# DigitalClockV2sch.net
KiCad netlist of a schematic drawn in Altium Designer
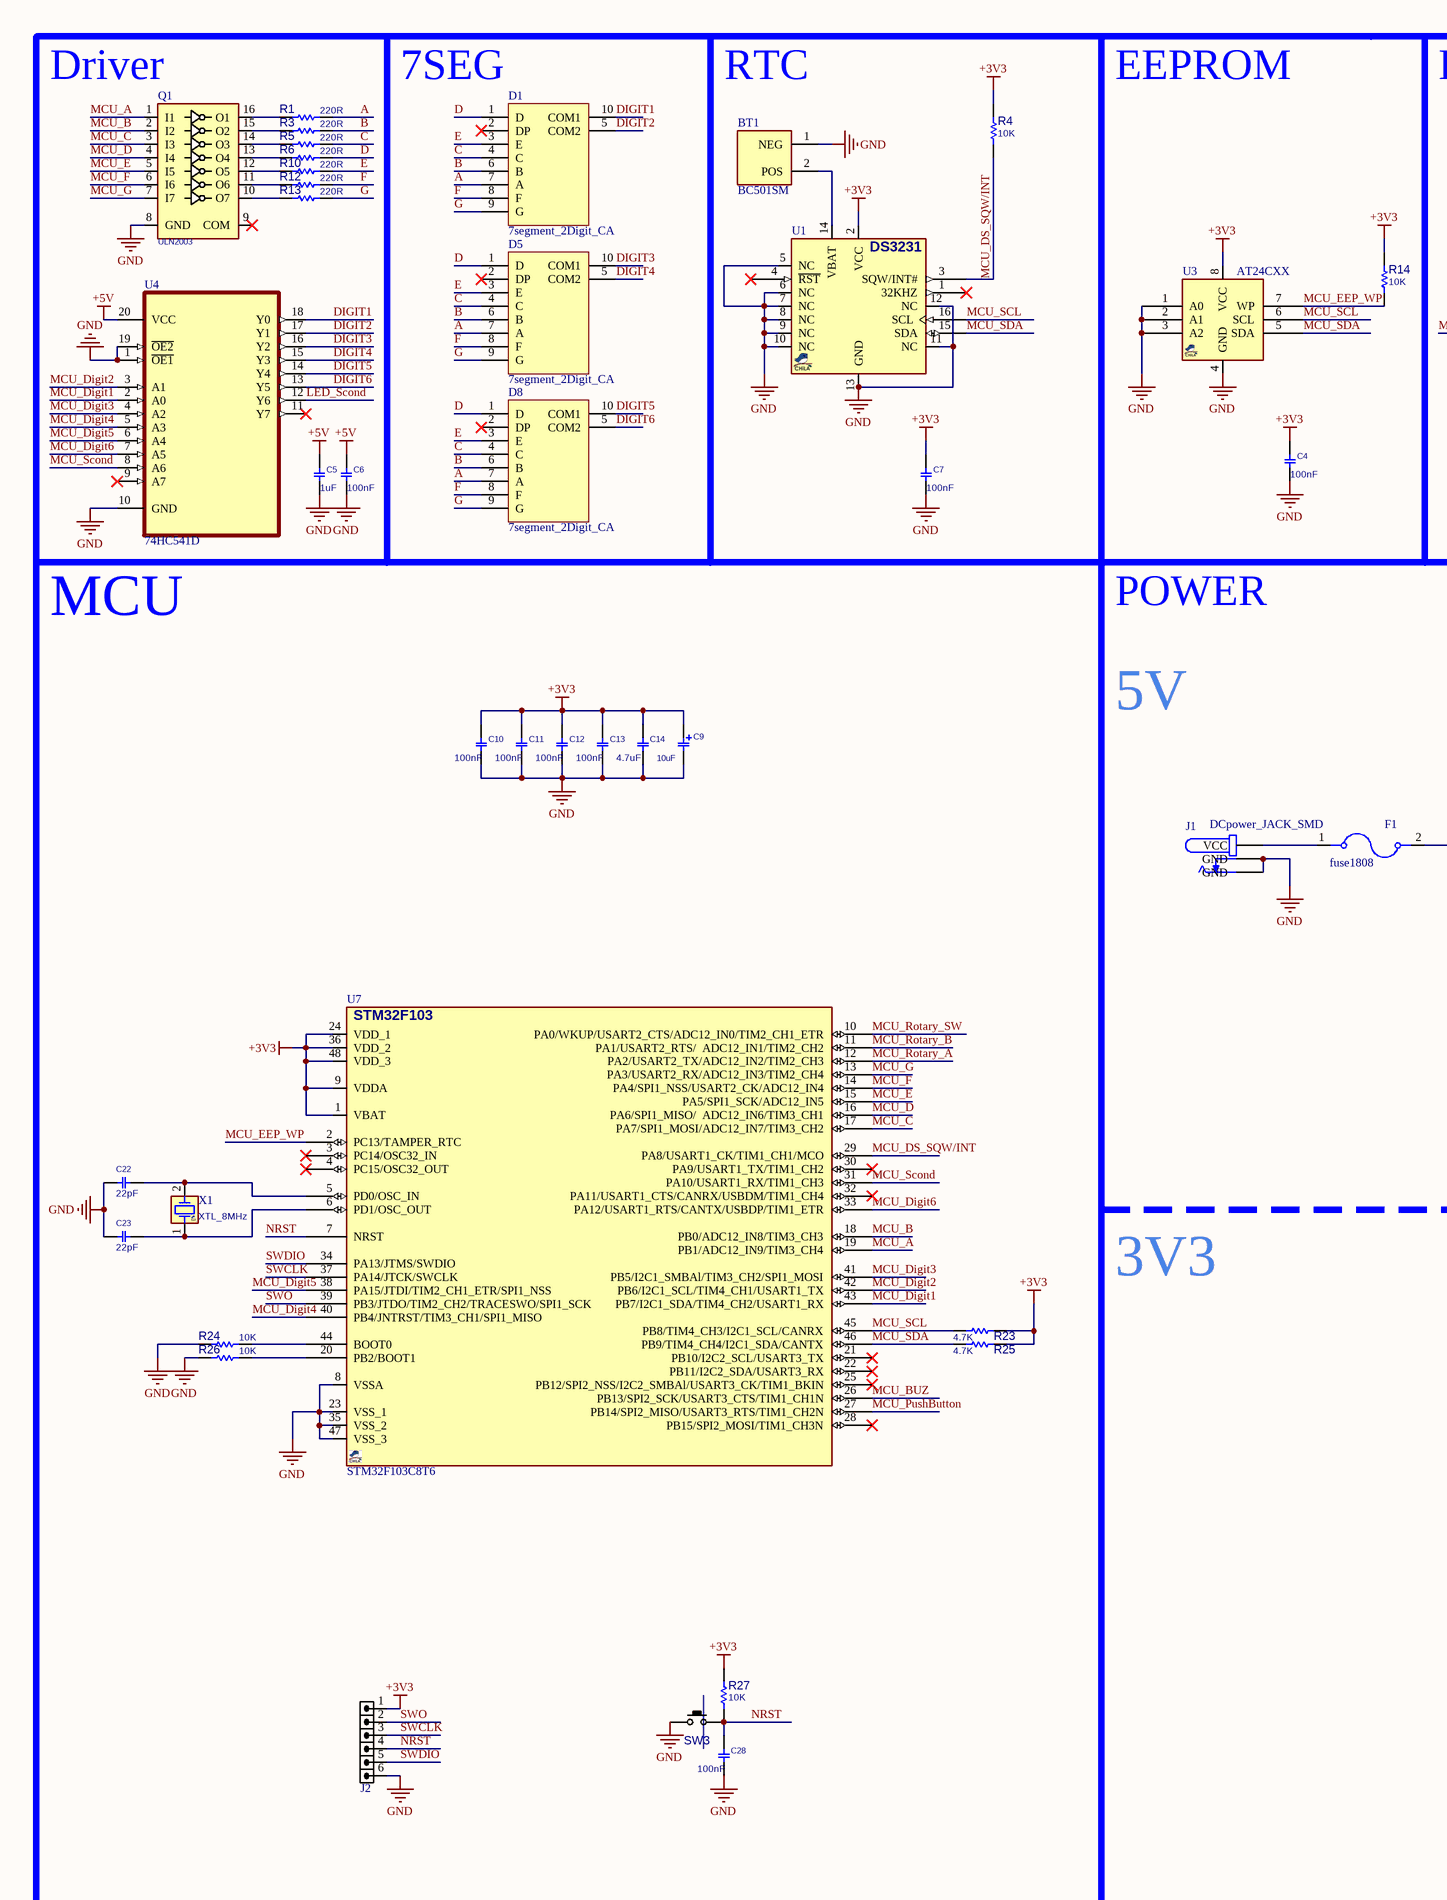
[diagram p0: DigitalClockV2sch.SchDoc, left]
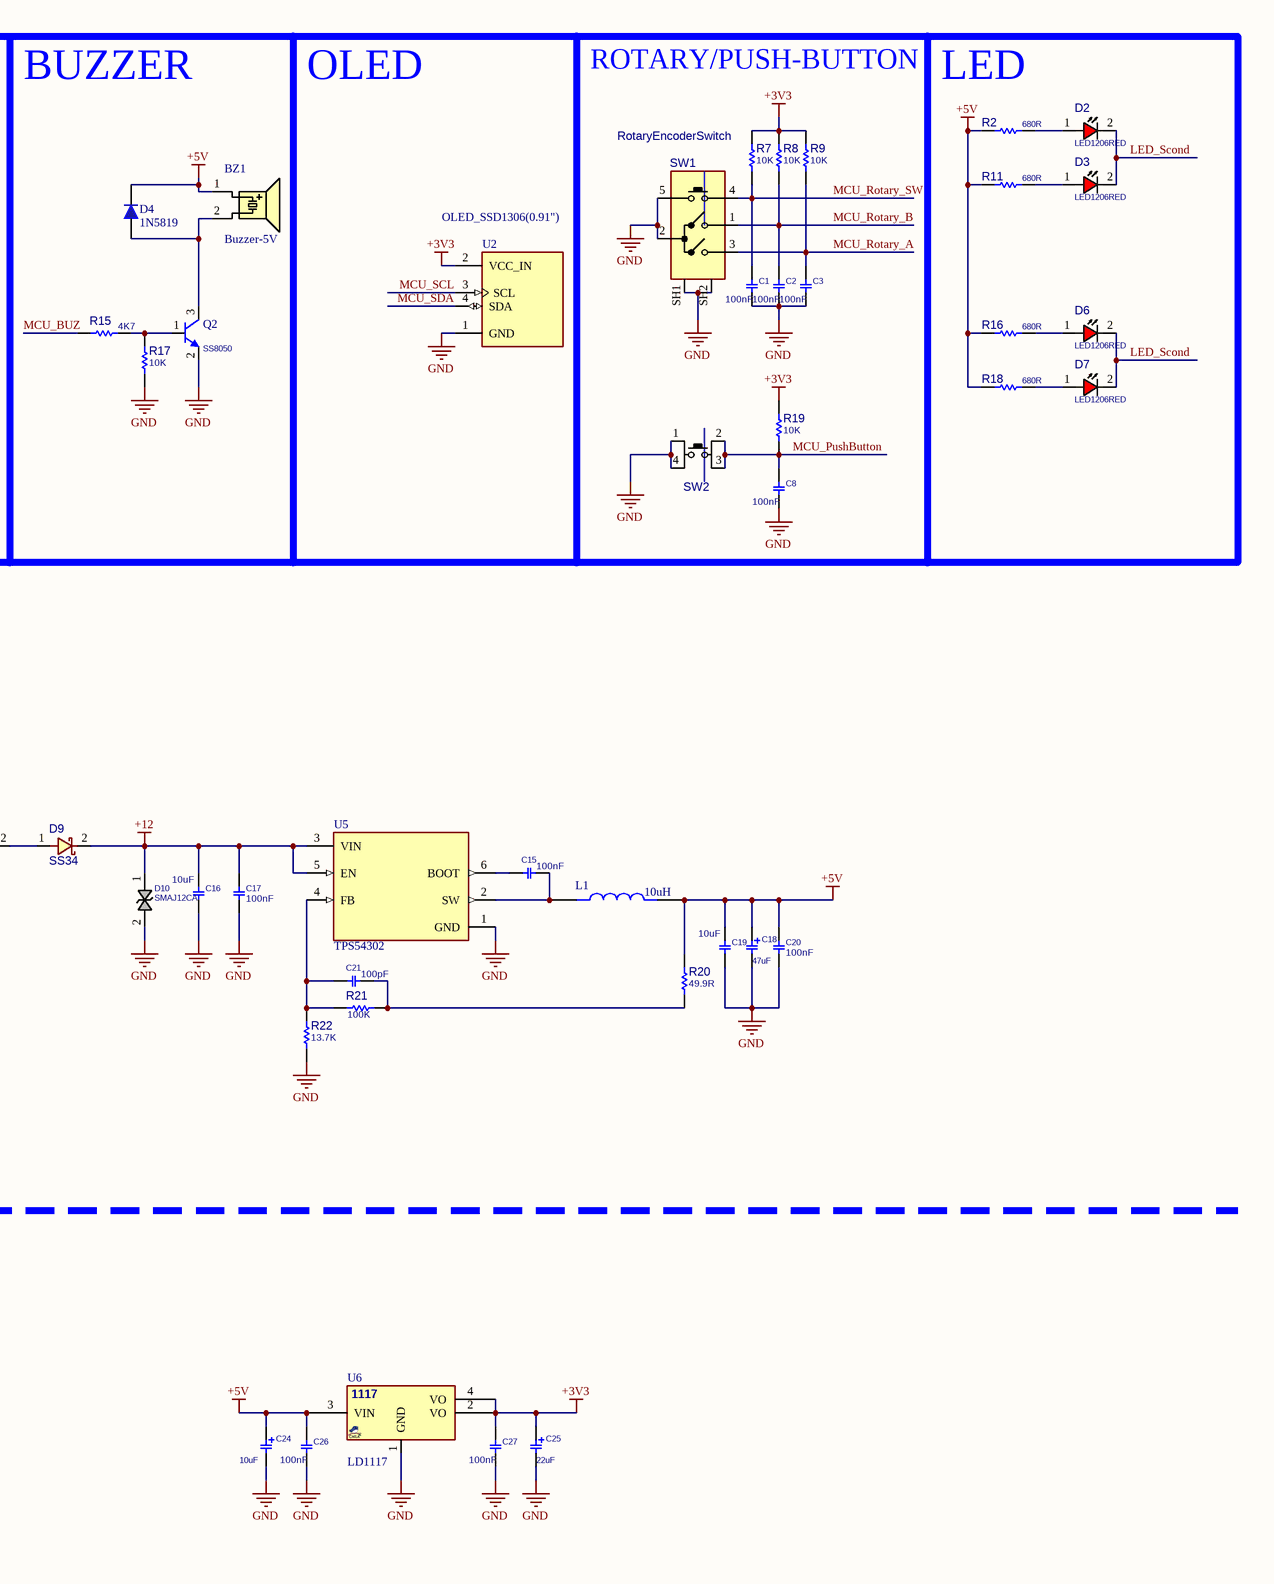
[diagram p1: DigitalClockV2sch.SchDoc, right]

(export (version "E")
  (design (tool "Eeschema 10.0.6"))
  (components
    (comp (ref "BT1") (value "BC501SM") (footprint "BC501SM") (libsource (lib "Mehrdad") (part "BC501SM")))
    (comp (ref "BZ1")
      (value "Buzzer-5V")
      (footprint "Buzzer-9mm")
      (description "Buzzer 5V 9mm (between pins 5.5mm)")
      (libsource (lib "Mehrdad") (part "Buzzer-9mm"))
    )
    (comp (ref "C1")
      (value "100nF")
      (footprint "C0603")
      (description "CAP, MLCC")
      (fields (field (name "MANF_P#") "MANF_PART#"))
      (libsource (lib "passive_smd") (part "CAP_SMD_MLCC_0603"))
    )
    (comp (ref "C2")
      (value "100nF")
      (footprint "C0603")
      (description "CAP, MLCC")
      (fields (field (name "MANF_P#") "MANF_PART#"))
      (libsource (lib "passive_smd") (part "CAP_SMD_MLCC_0603"))
    )
    (comp (ref "C3")
      (value "100nF")
      (footprint "C0603")
      (description "CAP, MLCC")
      (fields (field (name "MANF_P#") "MANF_PART#"))
      (libsource (lib "passive_smd") (part "CAP_SMD_MLCC_0603"))
    )
    (comp (ref "C4")
      (value "100nF")
      (footprint "C0805")
      (description "CAP, MLCC")
      (fields (field (name "MANF_P#") "MANF_PART#"))
      (libsource (lib "passive_smd") (part "CAP_SMD_MLCC_0805"))
    )
    (comp (ref "C5")
      (value "1uF")
      (footprint "C0805")
      (description "CAP, MLCC")
      (fields (field (name "MANF_P#") "MANF_PART#"))
      (libsource (lib "passive_smd") (part "CAP_SMD_MLCC_0805"))
    )
    (comp (ref "C6")
      (value "100nF")
      (footprint "C0805")
      (description "CAP, MLCC")
      (fields (field (name "MANF_P#") "MANF_PART#"))
      (libsource (lib "passive_smd") (part "CAP_SMD_MLCC_0805"))
    )
    (comp (ref "C7")
      (value "100nF")
      (footprint "C0805")
      (description "CAP, MLCC")
      (fields (field (name "MANF_P#") "MANF_PART#"))
      (libsource (lib "passive_smd") (part "CAP_SMD_MLCC_0805"))
    )
    (comp (ref "C8")
      (value "100nF")
      (footprint "C0603")
      (description "CAP, MLCC")
      (fields (field (name "MANF_P#") "MANF_PART#"))
      (libsource (lib "passive_smd") (part "CAP_SMD_MLCC_0603"))
    )
    (comp (ref "C9")
      (value "10uF")
      (footprint "C_TN_3216")
      (description "CAP, SMD, TAN")
      (fields (field (name "MANF") "VISHAY") (field (name "MANF_P#") "T55A106M010C0300"))
      (libsource (lib "passive_smd") (part "CAP_SMD_TAN_10uF_10V"))
    )
    (comp (ref "C10")
      (value "100nF")
      (footprint "C0603")
      (description "CAP, MLCC")
      (fields (field (name "MANF_P#") "MANF_PART#"))
      (libsource (lib "passive_smd") (part "CAP_SMD_MLCC_0603"))
    )
    (comp (ref "C11")
      (value "100nF")
      (footprint "C0603")
      (description "CAP, MLCC")
      (fields (field (name "MANF_P#") "MANF_PART#"))
      (libsource (lib "passive_smd") (part "CAP_SMD_MLCC_0603"))
    )
    (comp (ref "C12")
      (value "100nF")
      (footprint "C0603")
      (description "CAP, MLCC")
      (fields (field (name "MANF_P#") "MANF_PART#"))
      (libsource (lib "passive_smd") (part "CAP_SMD_MLCC_0603"))
    )
    (comp (ref "C13")
      (value "100nF")
      (footprint "C0603")
      (description "CAP, MLCC")
      (fields (field (name "MANF_P#") "MANF_PART#"))
      (libsource (lib "passive_smd") (part "CAP_SMD_MLCC_0603"))
    )
    (comp (ref "C14")
      (value "4.7uF")
      (footprint "C0603")
      (description "CAP, MLCC")
      (fields (field (name "MANF_P#") "MANF_PART#"))
      (libsource (lib "passive_smd") (part "CAP_SMD_MLCC_0603"))
    )
    (comp (ref "C15")
      (value "100nF")
      (footprint "C0603")
      (description "CAP, MLCC")
      (fields (field (name "MANF_P#") "MANF_PART#"))
      (libsource (lib "passive_smd") (part "CAP_SMD_MLCC_0603"))
    )
    (comp (ref "C16")
      (value "10uF")
      (footprint "C1206")
      (description "CAP, MLCC")
      (fields (field (name "MANF_P#") "MANF_PART#"))
      (libsource (lib "passive_smd") (part "CAP_SMD_MLCC_1206"))
    )
    (comp (ref "C17")
      (value "100nF")
      (footprint "C1206")
      (description "CAP, MLCC")
      (fields (field (name "MANF_P#") "MANF_PART#"))
      (libsource (lib "passive_smd") (part "CAP_SMD_MLCC_1206"))
    )
    (comp (ref "C18")
      (value "47uF")
      (footprint "C_TN_3216")
      (description "CAP, SMD, TAN")
      (fields (field (name "MANF") "VISHAY") (field (name "MANF_P#") "T55A106M010C0300"))
      (libsource (lib "passive_smd") (part "CAP_SMD_TAN_10uF_10V"))
    )
    (comp (ref "C19")
      (value "10uF")
      (footprint "C1206")
      (description "CAP, MLCC")
      (fields (field (name "MANF_P#") "MANF_PART#"))
      (libsource (lib "passive_smd") (part "CAP_SMD_MLCC_1206"))
    )
    (comp (ref "C20")
      (value "100nF")
      (footprint "C1206")
      (description "CAP, MLCC")
      (fields (field (name "MANF_P#") "MANF_PART#"))
      (libsource (lib "passive_smd") (part "CAP_SMD_MLCC_1206"))
    )
    (comp (ref "C21")
      (value "100pF")
      (footprint "C0603")
      (description "CAP, MLCC")
      (fields (field (name "MANF_P#") "MANF_PART#"))
      (libsource (lib "passive_smd") (part "CAP_SMD_MLCC_0603"))
    )
    (comp (ref "C22")
      (value "22pF")
      (footprint "C0603")
      (description "CAP, MLCC")
      (fields (field (name "MANF_P#") "MANF_PART#"))
      (libsource (lib "passive_smd") (part "CAP_SMD_MLCC_0603"))
    )
    (comp (ref "C23")
      (value "22pF")
      (footprint "C0603")
      (description "CAP, MLCC")
      (fields (field (name "MANF_P#") "MANF_PART#"))
      (libsource (lib "passive_smd") (part "CAP_SMD_MLCC_0603"))
    )
    (comp (ref "C24")
      (value "10uF")
      (footprint "C_TN_3216")
      (description "CAP, SMD, TAN")
      (fields (field (name "MANF") "VISHAY") (field (name "MANF_P#") "T55A106M010C0300"))
      (libsource (lib "passive_smd") (part "CAP_SMD_TAN_10uF_10V"))
    )
    (comp (ref "C25")
      (value "22uF")
      (footprint "C_TN_3216")
      (description "CAP, SMD, TAN")
      (fields (field (name "MANF") "VISHAY") (field (name "MANF_P#") "T55A106M010C0300"))
      (libsource (lib "passive_smd") (part "CAP_SMD_TAN_10uF_10V"))
    )
    (comp (ref "C26")
      (value "100nF")
      (footprint "C0603")
      (description "CAP, MLCC")
      (fields (field (name "MANF_P#") "MANF_PART#"))
      (libsource (lib "passive_smd") (part "CAP_SMD_MLCC_0603"))
    )
    (comp (ref "C27")
      (value "100nF")
      (footprint "C0603")
      (description "CAP, MLCC")
      (fields (field (name "MANF_P#") "MANF_PART#"))
      (libsource (lib "passive_smd") (part "CAP_SMD_MLCC_0603"))
    )
    (comp (ref "C28")
      (value "100nF")
      (footprint "C0603")
      (description "CAP, MLCC")
      (fields (field (name "MANF_P#") "MANF_PART#"))
      (libsource (lib "passive_smd") (part "CAP_SMD_MLCC_0603"))
    )
    (comp (ref "D1")
      (value "7segment_2Digit_CA")
      (footprint "7segment_2Digit_CA")
      (description "7segment_2Digit_CA (4021BS) 20.1 * 16")
      (libsource (lib "Mehrdad") (part "7segment_2Digit_CA"))
    )
    (comp (ref "D2")
      (value "LED1206RED")
      (footprint "LED1206RED")
      (description "LED, SMD, 1206, RED")
      (fields (field (name "MANF") "MANF") (field (name "MANF_P#") "MANF_PART#"))
      (libsource (lib "led(diode)") (part "LED_SMD_1206_RED"))
    )
    (comp (ref "D3")
      (value "LED1206RED")
      (footprint "LED1206RED")
      (description "LED, SMD, 1206, RED")
      (fields (field (name "MANF") "MANF") (field (name "MANF_P#") "MANF_PART#"))
      (libsource (lib "led(diode)") (part "LED_SMD_1206_RED"))
    )
    (comp (ref "D4")
      (value "1N5819")
      (footprint "DO-214AC(SMA)")
      (libsource (lib "ZetaBoard Altium Lib 14000319") (part "1N5819(SS14)"))
    )
    (comp (ref "D5")
      (value "7segment_2Digit_CA")
      (footprint "7segment_2Digit_CA")
      (description "7segment_2Digit_CA (4021BS) 20.1 * 16")
      (libsource (lib "Mehrdad") (part "7segment_2Digit_CA"))
    )
    (comp (ref "D6")
      (value "LED1206RED")
      (footprint "LED1206RED")
      (description "LED, SMD, 1206, RED")
      (fields (field (name "MANF") "MANF") (field (name "MANF_P#") "MANF_PART#"))
      (libsource (lib "led(diode)") (part "LED_SMD_1206_RED"))
    )
    (comp (ref "D7")
      (value "LED1206RED")
      (footprint "LED1206RED")
      (description "LED, SMD, 1206, RED")
      (fields (field (name "MANF") "MANF") (field (name "MANF_P#") "MANF_PART#"))
      (libsource (lib "led(diode)") (part "LED_SMD_1206_RED"))
    )
    (comp (ref "D8")
      (value "7segment_2Digit_CA")
      (footprint "7segment_2Digit_CA")
      (description "7segment_2Digit_CA (4021BS) 20.1 * 16")
      (libsource (lib "Mehrdad") (part "7segment_2Digit_CA"))
    )
    (comp (ref "D9")
      (value "SS34")
      (footprint "D_SMB")
      (description "DIODE, SCHOTTKY, 20V, 3A")
      (fields (field (name "MANF") "VISHAY"))
      (libsource (lib "diode") (part "DIODE_SMD_SCHOTTKY_SS34"))
    )
    (comp (ref "D10")
      (value "SMAJ12CA")
      (footprint "D_SMA")
      (description "TVS, ESD PROTECT, Bidirectional")
      (fields (field (name "MANF") "Littelfuse"))
      (libsource (lib "protect_tvs_esd_fuse") (part "TVS_SMAJ12CA"))
    )
    (comp (ref "F1") (value "fuse1808") (footprint "fuse1808") (libsource (lib "Mehrdad") (part "fuse1808")))
    (comp (ref "J1")
      (value "DCpower_JACK_SMD")
      (footprint "DCpower_JACK_SMD")
      (description "Connector, dc jack 5.5x2.5 mm, PCB mount, 90 degrees, silver plated, PA9T, SMT")
      (libsource (lib "Mehrdad") (part "DCpower_JACK_SMD"))
    )
    (comp (ref "J2")
      (value "HDR1X6")
      (footprint "HDR_M_1X6")
      (description "CONN, HEADER, Male, pitch: 2.54mm, 6POS")
      (libsource (lib "conn_header_2.54mm_st") (part "HDR_M_1X6"))
    )
    (comp (ref "L1")
      (value "10uH")
      (footprint "TDK SMD inductor 7mm * 7mm")
      (description "10 ÂµH Shielded Drum Core, Wirewound Inductor 1.78 A 43.2mOhm Max Nonstandard")
      (libsource (lib "Mehrdad") (part "TDK SMD inductor 7mm * 7mm"))
    )
    (comp (ref "Q1")
      (value "ULN2003")
      (footprint "SO_16")
      (description "Darlington, 7-CH, 50V, 0.5A, 5V TTL/CMOS")
      (fields (field (name "MANF_P#") "ULN2003D1") (field (name "MANF") "ST"))
      (libsource (lib "transistor_bjt") (part "ULN2003_SOP16_ST"))
    )
    (comp (ref "Q2")
      (value "SS8050")
      (footprint "SOT23_3")
      (description "BJT, NPN, 25v, 1.5A, SMD, SOT23")
      (fields (field (name "MANF") "GALAXY"))
      (libsource (lib "transistor_bjt") (part "NPN_SS8050_SOT23"))
    )
    (comp (ref "R1")
      (value "220R")
      (footprint "R0805")
      (description "RESISTOR, SMD")
      (libsource (lib "passive_smd") (part "RES_SMD_0805"))
    )
    (comp (ref "R2")
      (value "680R")
      (footprint "R1206")
      (description "RESISTOR, SMD")
      (libsource (lib "passive_smd") (part "RES_SMD_1206"))
    )
    (comp (ref "R3")
      (value "220R")
      (footprint "R0805")
      (description "RESISTOR, SMD")
      (libsource (lib "passive_smd") (part "RES_SMD_0805"))
    )
    (comp (ref "R4")
      (value "10K")
      (footprint "R0603")
      (description "RESISTOR, SMD")
      (libsource (lib "passive_smd") (part "RES_SMD_0603"))
    )
    (comp (ref "R5")
      (value "220R")
      (footprint "R0805")
      (description "RESISTOR, SMD")
      (libsource (lib "passive_smd") (part "RES_SMD_0805"))
    )
    (comp (ref "R6")
      (value "220R")
      (footprint "R0805")
      (description "RESISTOR, SMD")
      (libsource (lib "passive_smd") (part "RES_SMD_0805"))
    )
    (comp (ref "R7")
      (value "10K")
      (footprint "R0603")
      (description "RESISTOR, SMD")
      (libsource (lib "passive_smd") (part "RES_SMD_0603"))
    )
    (comp (ref "R8")
      (value "10K")
      (footprint "R0603")
      (description "RESISTOR, SMD")
      (libsource (lib "passive_smd") (part "RES_SMD_0603"))
    )
    (comp (ref "R9")
      (value "10K")
      (footprint "R0603")
      (description "RESISTOR, SMD")
      (libsource (lib "passive_smd") (part "RES_SMD_0603"))
    )
    (comp (ref "R10")
      (value "220R")
      (footprint "R0805")
      (description "RESISTOR, SMD")
      (libsource (lib "passive_smd") (part "RES_SMD_0805"))
    )
    (comp (ref "R11")
      (value "680R")
      (footprint "R1206")
      (description "RESISTOR, SMD")
      (libsource (lib "passive_smd") (part "RES_SMD_1206"))
    )
    (comp (ref "R12")
      (value "220R")
      (footprint "R0805")
      (description "RESISTOR, SMD")
      (libsource (lib "passive_smd") (part "RES_SMD_0805"))
    )
    (comp (ref "R13")
      (value "220R")
      (footprint "R0805")
      (description "RESISTOR, SMD")
      (libsource (lib "passive_smd") (part "RES_SMD_0805"))
    )
    (comp (ref "R14")
      (value "10K")
      (footprint "R0805")
      (description "RESISTOR, SMD")
      (libsource (lib "passive_smd") (part "RES_SMD_0805"))
    )
    (comp (ref "R15")
      (value "4K7")
      (footprint "R0603")
      (description "RESISTOR, SMD")
      (libsource (lib "passive_smd") (part "RES_SMD_0603"))
    )
    (comp (ref "R16")
      (value "680R")
      (footprint "R1206")
      (description "RESISTOR, SMD")
      (libsource (lib "passive_smd") (part "RES_SMD_1206"))
    )
    (comp (ref "R17")
      (value "10K")
      (footprint "R0603")
      (description "RESISTOR, SMD")
      (libsource (lib "passive_smd") (part "RES_SMD_0603"))
    )
    (comp (ref "R18")
      (value "680R")
      (footprint "R1206")
      (description "RESISTOR, SMD")
      (libsource (lib "passive_smd") (part "RES_SMD_1206"))
    )
    (comp (ref "R19")
      (value "10K")
      (footprint "R0603")
      (description "RESISTOR, SMD")
      (libsource (lib "passive_smd") (part "RES_SMD_0603"))
    )
    (comp (ref "R20")
      (value "49.9R")
      (footprint "R0603")
      (description "RESISTOR, SMD")
      (libsource (lib "passive_smd") (part "RES_SMD_0603"))
    )
    (comp (ref "R21")
      (value "100K")
      (footprint "R0603")
      (description "RESISTOR, SMD")
      (libsource (lib "passive_smd") (part "RES_SMD_0603"))
    )
    (comp (ref "R22")
      (value "13.7K")
      (footprint "R0805")
      (description "RESISTOR, SMD")
      (libsource (lib "passive_smd") (part "RES_SMD_0805"))
    )
    (comp (ref "R23")
      (value "4.7K")
      (footprint "R0805")
      (description "RESISTOR, SMD")
      (libsource (lib "passive_smd") (part "RES_SMD_0805"))
    )
    (comp (ref "R24")
      (value "10K")
      (footprint "R0603")
      (description "RESISTOR, SMD")
      (libsource (lib "passive_smd") (part "RES_SMD_0603"))
    )
    (comp (ref "R25")
      (value "4.7K")
      (footprint "R0805")
      (description "RESISTOR, SMD")
      (libsource (lib "passive_smd") (part "RES_SMD_0805"))
    )
    (comp (ref "R26")
      (value "10K")
      (footprint "R0603")
      (description "RESISTOR, SMD")
      (libsource (lib "passive_smd") (part "RES_SMD_0603"))
    )
    (comp (ref "R27")
      (value "10K")
      (footprint "R0603")
      (description "RESISTOR, SMD")
      (libsource (lib "passive_smd") (part "RES_SMD_0603"))
    )
    (comp (ref "SW1")
      (value "RotaryEncoderSwitch")
      (footprint "SWROT_11MM")
      (description "SWITCH, ROTARY Encoder, 11mm Metal Shaft")
      (fields (field (name "MANF") "Alpha") (field (name "MANF_PART#") "RE111F-41B3N-15F-20P"))
      (libsource (lib "switch_rotary_encoder") (part "SWROT_11MM"))
    )
    (comp (ref "SW2")
      (value "PUSHBUTTON")
      (footprint "SWPBT_SPDT_6X6X17SKHH")
      (description "SWITCH, PUSH BUTTON, TACTILE, THD, SPDT, 6X6X17mm")
      (fields (field (name "MANF") "ALPS") (field (name "MANF_P#") "SKHHDHA010"))
      (libsource (lib "switch_tact_PUSHB") (part "SWPBT_SPDT_6X6X17_SKHHDHA010"))
    )
    (comp (ref "SW3")
      (value "PUSHBUTTON")
      (footprint "SWPBS_SPST_6X3X2")
      (description "SWITCH, PUSH BUTTON, TACTILE, SMD, SPST, 6X3.5X2.5mm")
      (fields (field (name "MANF") "C&K") (field (name "MANF_P#") "RS-282G05A3-SM RT"))
      (libsource (lib "switch_tact_PUSHB") (part "SWPBS_SPST_6X3X2_RS282"))
    )
    (comp (ref "U1")
      (value "DS3231")
      (footprint "SO_16_W")
      (description "Real-Time Clock, I2C, +IntCryst")
      (fields (field (name "MANF") "Maxim Integrated") (field (name "MANF_P#") "DS3231SN#"))
      (libsource (lib "rtc") (part "DS3231_SOP16W"))
    )
    (comp (ref "U2")
      (value "OLED_SSD1306(0.91\")")
      (footprint "OLED_Display 0.91\" 32*128")
      (libsource (lib "Mehrdad") (part "OLED_Display 0.91{dblquote} 32*128"))
    )
    (comp (ref "U3")
      (value "AT24CXX")
      (footprint "SO_8")
      (description "EEPROM, I2C,")
      (libsource (lib "memory_eeprom_I2C") (part "EEPROM_I2C_AT24CXX_SOP8"))
    )
    (comp (ref "U4")
      (value "74HC541D")
      (footprint "74HC541D")
      (description "Buffer, Non-Inverting 1 Element 8 Bit per Element 3-State Output 20-SOIC")
      (libsource (lib "Mehrdad") (part "74HC541D"))
    )
    (comp (ref "U5")
      (value "TPS54302")
      (footprint "TPS54302")
      (description "4.5-V to 28-V Input, 3-A Output, EMI Friendly\r\nSynchronous Step-Down Converter")
      (libsource (lib "Mehrdad") (part "TPS54302"))
    )
    (comp (ref "U6")
      (value "LD1117")
      (footprint "SOT223_4")
      (description "REG, Linear, LDO1V, 0.8A, SOT-223")
      (fields
        (field (name "MANF_P#") "LD1117, LM1117, AMS1117, TLV1117, REG1117, NCP1117, LT1117, SPX1117")
        (field (name "MANF") "TI, ON, ST")
      )
      (libsource (lib "pwr_reg_linear_1117") (part "VREG_1117_SOT223"))
    )
    (comp (ref "U7")
      (value "STM32F103C8T6")
      (footprint "STM32F103C8T6")
      (description "MCU, STM32 ARM 32-bit, Cortex M3, 64KB FLASH, 20KB SRAM")
      (libsource (lib "Mehrdad") (part "STM32F103C8T6"))
    )
    (comp (ref "X1")
      (value "XTL_8MHz")
      (footprint "XTL_2_11X5")
      (description "Crystal MOST POPULAR ABL HC49 PACKAGE")
      (fields (field (name "MANF") "ABRACON") (field (name "MANF_P#") "ABLS-8.000MHZ-B4-T"))
      (libsource (lib "crystal") (part "XTL_2_HC49_8MHz_SMD"))
    )
  )
  (nets
    (net (code "1") (name "+3V3") (class "Default")
      (node (ref "C10") (pin "2") (pinfunction "2_2") (pintype "passive"))
      (node (ref "C11") (pin "2") (pinfunction "2_2") (pintype "passive"))
      (node (ref "C12") (pin "2") (pinfunction "2_2") (pintype "passive"))
      (node (ref "C13") (pin "2") (pinfunction "2_2") (pintype "passive"))
      (node (ref "C14") (pin "2") (pinfunction "2_2") (pintype "passive"))
      (node (ref "C25") (pin "1") (pinfunction "1_1") (pintype "passive"))
      (node (ref "C27") (pin "2") (pinfunction "2_2") (pintype "passive"))
      (node (ref "C4") (pin "2") (pinfunction "2_2") (pintype "passive"))
      (node (ref "C7") (pin "2") (pinfunction "2_2") (pintype "passive"))
      (node (ref "C9") (pin "1") (pinfunction "1_1") (pintype "passive"))
      (node (ref "J2") (pin "1") (pinfunction "1_1") (pintype "passive"))
      (node (ref "R14") (pin "1") (pinfunction "1_1") (pintype "passive"))
      (node (ref "R19") (pin "2") (pinfunction "2_2") (pintype "passive"))
      (node (ref "R23") (pin "2") (pinfunction "2_2") (pintype "passive"))
      (node (ref "R25") (pin "2") (pinfunction "2_2") (pintype "passive"))
      (node (ref "R27") (pin "1") (pinfunction "1_1") (pintype "passive"))
      (node (ref "R4") (pin "2") (pinfunction "2_2") (pintype "passive"))
      (node (ref "R7") (pin "2") (pinfunction "2_2") (pintype "passive"))
      (node (ref "R8") (pin "2") (pinfunction "2_2") (pintype "passive"))
      (node (ref "R9") (pin "2") (pinfunction "2_2") (pintype "passive"))
      (node (ref "U1") (pin "2") (pinfunction "VCC_2") (pintype "power_in"))
      (node (ref "U2") (pin "2") (pinfunction "VCC_IN_2") (pintype "power_in"))
      (node (ref "U3") (pin "8") (pinfunction "VCC_8") (pintype "passive"))
      (node (ref "U6") (pin "2") (pinfunction "VO_2") (pintype "passive"))
      (node (ref "U6") (pin "4") (pinfunction "VO_4") (pintype "passive"))
      (node (ref "U7") (pin "1") (pinfunction "VBAT_1") (pintype "passive"))
      (node (ref "U7") (pin "24") (pinfunction "VDD_1_24") (pintype "passive"))
      (node (ref "U7") (pin "36") (pinfunction "VDD_2_36") (pintype "passive"))
      (node (ref "U7") (pin "48") (pinfunction "VDD_3_48") (pintype "passive"))
      (node (ref "U7") (pin "9") (pinfunction "VDDA_9") (pintype "passive"))
    )
    (net (code "2") (name "+5V") (class "Default")
      (node (ref "BZ1") (pin "1") (pinfunction "A_1") (pintype "passive"))
      (node (ref "C18") (pin "1") (pinfunction "1_1") (pintype "passive"))
      (node (ref "C19") (pin "2") (pinfunction "2_2") (pintype "passive"))
      (node (ref "C20") (pin "2") (pinfunction "2_2") (pintype "passive"))
      (node (ref "C24") (pin "1") (pinfunction "1_1") (pintype "passive"))
      (node (ref "C26") (pin "2") (pinfunction "2_2") (pintype "passive"))
      (node (ref "C5") (pin "2") (pinfunction "2_2") (pintype "passive"))
      (node (ref "C6") (pin "2") (pinfunction "2_2") (pintype "passive"))
      (node (ref "D4") (pin "2") (pintype "passive"))
      (node (ref "L1") (pin "2") (pinfunction "2_2") (pintype "passive"))
      (node (ref "R11") (pin "1") (pinfunction "1_1") (pintype "passive"))
      (node (ref "R16") (pin "1") (pinfunction "1_1") (pintype "passive"))
      (node (ref "R18") (pin "1") (pinfunction "1_1") (pintype "passive"))
      (node (ref "R2") (pin "1") (pinfunction "1_1") (pintype "passive"))
      (node (ref "R20") (pin "1") (pinfunction "1_1") (pintype "passive"))
      (node (ref "U4") (pin "20") (pinfunction "VCC_20") (pintype "power_in"))
      (node (ref "U6") (pin "3") (pinfunction "VIN_3") (pintype "passive"))
    )
    (net (code "3") (name "+12") (class "Default")
      (node (ref "C16") (pin "2") (pinfunction "2_2") (pintype "passive"))
      (node (ref "C17") (pin "2") (pinfunction "2_2") (pintype "passive"))
      (node (ref "D10") (pin "1") (pinfunction "1_1") (pintype "passive"))
      (node (ref "D9") (pin "2") (pinfunction "2_2") (pintype "passive"))
      (node (ref "U5") (pin "3") (pinfunction "VIN_3") (pintype "power_in"))
      (node (ref "U5") (pin "5") (pinfunction "EN_5") (pintype "input"))
    )
    (net (code "4") (name "/A") (class "Default")
      (node (ref "D1") (pin "7") (pinfunction "A_7") (pintype "passive"))
      (node (ref "D5") (pin "7") (pinfunction "A_7") (pintype "passive"))
      (node (ref "D8") (pin "7") (pinfunction "A_7") (pintype "passive"))
      (node (ref "R1") (pin "2") (pinfunction "2_2") (pintype "passive"))
    )
    (net (code "5") (name "/B") (class "Default")
      (node (ref "D1") (pin "6") (pinfunction "B_6") (pintype "passive"))
      (node (ref "D5") (pin "6") (pinfunction "B_6") (pintype "passive"))
      (node (ref "D8") (pin "6") (pinfunction "B_6") (pintype "passive"))
      (node (ref "R3") (pin "2") (pinfunction "2_2") (pintype "passive"))
    )
    (net (code "6") (name "/C") (class "Default")
      (node (ref "D1") (pin "4") (pinfunction "C_4") (pintype "passive"))
      (node (ref "D5") (pin "4") (pinfunction "C_4") (pintype "passive"))
      (node (ref "D8") (pin "4") (pinfunction "C_4") (pintype "passive"))
      (node (ref "R5") (pin "2") (pinfunction "2_2") (pintype "passive"))
    )
    (net (code "7") (name "/D") (class "Default")
      (node (ref "D1") (pin "1") (pinfunction "D_1") (pintype "passive"))
      (node (ref "D5") (pin "1") (pinfunction "D_1") (pintype "passive"))
      (node (ref "D8") (pin "1") (pinfunction "D_1") (pintype "passive"))
      (node (ref "R6") (pin "2") (pinfunction "2_2") (pintype "passive"))
    )
    (net (code "8") (name "/DIGIT1") (class "Default")
      (node (ref "D1") (pin "10") (pinfunction "COM1_10") (pintype "passive"))
      (node (ref "U4") (pin "18") (pinfunction "Y0_18") (pintype "output"))
    )
    (net (code "9") (name "/DIGIT2") (class "Default")
      (node (ref "D1") (pin "5") (pinfunction "COM2_5") (pintype "passive"))
      (node (ref "U4") (pin "17") (pinfunction "Y1_17") (pintype "output"))
    )
    (net (code "10") (name "/DIGIT3") (class "Default")
      (node (ref "D5") (pin "10") (pinfunction "COM1_10") (pintype "passive"))
      (node (ref "U4") (pin "16") (pinfunction "Y2_16") (pintype "output"))
    )
    (net (code "11") (name "/DIGIT4") (class "Default")
      (node (ref "D5") (pin "5") (pinfunction "COM2_5") (pintype "passive"))
      (node (ref "U4") (pin "15") (pinfunction "Y3_15") (pintype "output"))
    )
    (net (code "12") (name "/DIGIT5") (class "Default")
      (node (ref "D8") (pin "10") (pinfunction "COM1_10") (pintype "passive"))
      (node (ref "U4") (pin "14") (pinfunction "Y4_14") (pintype "output"))
    )
    (net (code "13") (name "/DIGIT6") (class "Default")
      (node (ref "D8") (pin "5") (pinfunction "COM2_5") (pintype "passive"))
      (node (ref "U4") (pin "13") (pinfunction "Y5_13") (pintype "output"))
    )
    (net (code "14") (name "/E") (class "Default")
      (node (ref "D1") (pin "3") (pinfunction "E_3") (pintype "passive"))
      (node (ref "D5") (pin "3") (pinfunction "E_3") (pintype "passive"))
      (node (ref "D8") (pin "3") (pinfunction "E_3") (pintype "passive"))
      (node (ref "R10") (pin "2") (pinfunction "2_2") (pintype "passive"))
    )
    (net (code "15") (name "/F") (class "Default")
      (node (ref "D1") (pin "8") (pinfunction "F_8") (pintype "passive"))
      (node (ref "D5") (pin "8") (pinfunction "F_8") (pintype "passive"))
      (node (ref "D8") (pin "8") (pinfunction "F_8") (pintype "passive"))
      (node (ref "R12") (pin "2") (pinfunction "2_2") (pintype "passive"))
    )
    (net (code "16") (name "/G") (class "Default")
      (node (ref "D1") (pin "9") (pinfunction "G_9") (pintype "passive"))
      (node (ref "D5") (pin "9") (pinfunction "G_9") (pintype "passive"))
      (node (ref "D8") (pin "9") (pinfunction "G_9") (pintype "passive"))
      (node (ref "R13") (pin "2") (pinfunction "2_2") (pintype "passive"))
    )
    (net (code "17") (name "/LED_Scond") (class "Default")
      (node (ref "D2") (pin "2") (pinfunction "CATHODE_2") (pintype "passive"))
      (node (ref "D3") (pin "2") (pinfunction "CATHODE_2") (pintype "passive"))
      (node (ref "D6") (pin "2") (pinfunction "CATHODE_2") (pintype "passive"))
      (node (ref "D7") (pin "2") (pinfunction "CATHODE_2") (pintype "passive"))
      (node (ref "U4") (pin "12") (pinfunction "Y6_12") (pintype "output"))
    )
    (net (code "18") (name "/MCU_A") (class "Default")
      (node (ref "Q1") (pin "1") (pinfunction "I1_1") (pintype "passive"))
      (node (ref "U7") (pin "19") (pinfunction "PB1/ADC12_IN9/TIM3_CH4_19") (pintype "bidirectional"))
    )
    (net (code "19") (name "/MCU_B") (class "Default")
      (node (ref "Q1") (pin "2") (pinfunction "I2_2") (pintype "passive"))
      (node (ref "U7") (pin "18") (pinfunction "PB0/ADC12_IN8/TIM3_CH3_18") (pintype "bidirectional"))
    )
    (net (code "20") (name "/MCU_BUZ") (class "Default")
      (node (ref "R15") (pin "1") (pinfunction "1_1") (pintype "passive"))
      (node (ref "U7") (pin "26") (pinfunction "PB13/SPI2_SCK/USART3_CTS/TIM1_CH1N_26") (pintype "bidirectional"))
    )
    (net (code "21") (name "/MCU_C") (class "Default")
      (node (ref "Q1") (pin "3") (pinfunction "I3_3") (pintype "passive"))
      (node (ref "U7") (pin "17") (pinfunction "PA7/SPI1_MOSI/ADC12_IN7/TIM3_CH2_17") (pintype "bidirectional"))
    )
    (net (code "22") (name "/MCU_D") (class "Default")
      (node (ref "Q1") (pin "4") (pinfunction "I4_4") (pintype "passive"))
      (node (ref "U7") (pin "16") (pinfunction "PA6/SPI1_MISO/__ADC12_IN6/TIM3_CH1_16") (pintype "bidirectional"))
    )
    (net (code "23") (name "/MCU_DS_SQW{slash}INT") (class "Default")
      (node (ref "R4") (pin "1") (pinfunction "1_1") (pintype "passive"))
      (node (ref "U1") (pin "3") (pinfunction "SQW/INT#_3") (pintype "output"))
      (node (ref "U7") (pin "29") (pinfunction "PA8/USART1_CK/TIM1_CH1/MCO_29") (pintype "bidirectional"))
    )
    (net (code "24") (name "/MCU_Digit1") (class "Default")
      (node (ref "U4") (pin "2") (pinfunction "A0_2") (pintype "input"))
      (node (ref "U7") (pin "43") (pinfunction "PB7/I2C1_SDA/TIM4_CH2/USART1_RX_43") (pintype "bidirectional"))
    )
    (net (code "25") (name "/MCU_Digit2") (class "Default")
      (node (ref "U4") (pin "3") (pinfunction "A1_3") (pintype "input"))
      (node (ref "U7") (pin "42") (pinfunction "PB6/I2C1_SCL/TIM4_CH1/USART1_TX_42") (pintype "bidirectional"))
    )
    (net (code "26") (name "/MCU_Digit3") (class "Default")
      (node (ref "U4") (pin "4") (pinfunction "A2_4") (pintype "input"))
      (node (ref "U7") (pin "41") (pinfunction "PB5/I2C1_SMBAl/TIM3_CH2/SPI1_MOSI_41") (pintype "bidirectional"))
    )
    (net (code "27") (name "/MCU_Digit4") (class "Default")
      (node (ref "U4") (pin "5") (pinfunction "A3_5") (pintype "input"))
      (node (ref "U7") (pin "40") (pinfunction "PB4/JNTRST/TIM3_CH1/SPI1_MISO_40") (pintype "passive"))
    )
    (net (code "28") (name "/MCU_Digit5") (class "Default")
      (node (ref "U4") (pin "6") (pinfunction "A4_6") (pintype "input"))
      (node (ref "U7") (pin "38") (pinfunction "PA15/JTDI/TIM2_CH1_ETR/SPI1_NSS_38") (pintype "passive"))
    )
    (net (code "29") (name "/MCU_Digit6") (class "Default")
      (node (ref "U4") (pin "7") (pinfunction "A5_7") (pintype "input"))
      (node (ref "U7") (pin "33") (pinfunction "PA12/USART1_RTS/CANTX/USBDP/TIM1_ETR_33") (pintype "bidirectional"))
    )
    (net (code "30") (name "/MCU_E") (class "Default")
      (node (ref "Q1") (pin "5") (pinfunction "I5_5") (pintype "passive"))
      (node (ref "U7") (pin "15") (pinfunction "PA5/SPI1_SCK/ADC12_IN5_15") (pintype "bidirectional"))
    )
    (net (code "31") (name "/MCU_EEP_WP") (class "Default")
      (node (ref "R14") (pin "2") (pinfunction "2_2") (pintype "passive"))
      (node (ref "U3") (pin "7") (pinfunction "WP_7") (pintype "passive"))
      (node (ref "U7") (pin "2") (pinfunction "PC13/TAMPER_RTC_2") (pintype "bidirectional"))
    )
    (net (code "32") (name "/MCU_F") (class "Default")
      (node (ref "Q1") (pin "6") (pinfunction "I6_6") (pintype "passive"))
      (node (ref "U7") (pin "14") (pinfunction "PA4/SPI1_NSS/USART2_CK/ADC12_IN4_14") (pintype "bidirectional"))
    )
    (net (code "33") (name "/MCU_G") (class "Default")
      (node (ref "Q1") (pin "7") (pinfunction "I7_7") (pintype "passive"))
      (node (ref "U7") (pin "13") (pinfunction "PA3/USART2_RX/ADC12_IN3/TIM2_CH4_13") (pintype "bidirectional"))
    )
    (net (code "34") (name "/MCU_PushButton") (class "Default")
      (node (ref "C8") (pin "2") (pinfunction "2_2") (pintype "passive"))
      (node (ref "R19") (pin "1") (pinfunction "1_1") (pintype "passive"))
      (node (ref "SW2") (pin "2") (pinfunction "P3_2") (pintype "passive"))
      (node (ref "SW2") (pin "3") (pinfunction "P4_3") (pintype "passive"))
      (node (ref "U7") (pin "27") (pinfunction "PB14/SPI2_MISO/USART3_RTS/TIM1_CH2N_27") (pintype "bidirectional"))
    )
    (net (code "35") (name "/MCU_Rotary_A") (class "Default")
      (node (ref "C3") (pin "2") (pinfunction "2_2") (pintype "passive"))
      (node (ref "R9") (pin "1") (pinfunction "1_1") (pintype "passive"))
      (node (ref "SW1") (pin "3") (pinfunction "B_3") (pintype "passive"))
      (node (ref "U7") (pin "12") (pinfunction "PA2/USART2_TX/ADC12_IN2/TIM2_CH3_12") (pintype "bidirectional"))
    )
    (net (code "36") (name "/MCU_Rotary_B") (class "Default")
      (node (ref "C2") (pin "2") (pinfunction "2_2") (pintype "passive"))
      (node (ref "R8") (pin "1") (pinfunction "1_1") (pintype "passive"))
      (node (ref "SW1") (pin "1") (pinfunction "A_1") (pintype "passive"))
      (node (ref "U7") (pin "11") (pinfunction "PA1/USART2_RTS/__ADC12_IN1/TIM2_CH2_11") (pintype "bidirectional"))
    )
    (net (code "37") (name "/MCU_Rotary_SW") (class "Default")
      (node (ref "C1") (pin "2") (pinfunction "2_2") (pintype "passive"))
      (node (ref "R7") (pin "1") (pinfunction "1_1") (pintype "passive"))
      (node (ref "SW1") (pin "4") (pinfunction "E_4") (pintype "passive"))
      (node (ref "U7") (pin "10") (pinfunction "PA0/WKUP/USART2_CTS/ADC12_IN0/TIM2_CH1_ETR_10") (pintype "bidirectional"))
    )
    (net (code "38") (name "/MCU_SCL") (class "Default")
      (node (ref "R23") (pin "1") (pinfunction "1_1") (pintype "passive"))
      (node (ref "U1") (pin "16") (pinfunction "SCL_16") (pintype "input"))
      (node (ref "U2") (pin "3") (pinfunction "SCL_3") (pintype "input"))
      (node (ref "U3") (pin "6") (pinfunction "SCL_6") (pintype "passive"))
      (node (ref "U7") (pin "45") (pinfunction "PB8/TIM4_CH3/I2C1_SCL/CANRX_45") (pintype "bidirectional"))
    )
    (net (code "39") (name "/MCU_SDA") (class "Default")
      (node (ref "R25") (pin "1") (pinfunction "1_1") (pintype "passive"))
      (node (ref "U1") (pin "15") (pinfunction "SDA_15") (pintype "bidirectional"))
      (node (ref "U2") (pin "4") (pinfunction "SDA_4") (pintype "bidirectional"))
      (node (ref "U3") (pin "5") (pinfunction "SDA_5") (pintype "passive"))
      (node (ref "U7") (pin "46") (pinfunction "PB9/TIM4_CH4/I2C1_SDA/CANTX_46") (pintype "bidirectional"))
    )
    (net (code "40") (name "/MCU_Scond") (class "Default")
      (node (ref "U4") (pin "8") (pinfunction "A6_8") (pintype "input"))
      (node (ref "U7") (pin "31") (pinfunction "PA10/USART1_RX/TIM1_CH3_31") (pintype "bidirectional"))
    )
    (net (code "41") (name "/NRST") (class "Default")
      (node (ref "C28") (pin "2") (pinfunction "2_2") (pintype "passive"))
      (node (ref "J2") (pin "4") (pinfunction "4_4") (pintype "passive"))
      (node (ref "R27") (pin "2") (pinfunction "2_2") (pintype "passive"))
      (node (ref "SW3") (pin "2") (pinfunction "P3_2") (pintype "passive"))
      (node (ref "U7") (pin "7") (pinfunction "NRST_7") (pintype "passive"))
    )
    (net (code "42") (name "/SWCLK") (class "Default")
      (node (ref "J2") (pin "3") (pinfunction "3_3") (pintype "passive"))
      (node (ref "U7") (pin "37") (pinfunction "PA14/JTCK/SWCLK_37") (pintype "passive"))
    )
    (net (code "43") (name "/SWDIO") (class "Default")
      (node (ref "J2") (pin "5") (pinfunction "5_5") (pintype "passive"))
      (node (ref "U7") (pin "34") (pinfunction "PA13/JTMS/SWDIO_34") (pintype "passive"))
    )
    (net (code "44") (name "/SWO") (class "Default")
      (node (ref "J2") (pin "2") (pinfunction "2_2") (pintype "passive"))
      (node (ref "U7") (pin "39") (pinfunction "PB3/JTDO/TIM2_CH2/TRACESWO/SPI1_SCK_39") (pintype "passive"))
    )
    (net (code "45") (name "GND") (class "Default")
      (node (ref "BT1") (pin "1") (pinfunction "NEG_1") (pintype "passive"))
      (node (ref "C1") (pin "1") (pinfunction "1_1") (pintype "passive"))
      (node (ref "C10") (pin "1") (pinfunction "1_1") (pintype "passive"))
      (node (ref "C11") (pin "1") (pinfunction "1_1") (pintype "passive"))
      (node (ref "C12") (pin "1") (pinfunction "1_1") (pintype "passive"))
      (node (ref "C13") (pin "1") (pinfunction "1_1") (pintype "passive"))
      (node (ref "C14") (pin "1") (pinfunction "1_1") (pintype "passive"))
      (node (ref "C16") (pin "1") (pinfunction "1_1") (pintype "passive"))
      (node (ref "C17") (pin "1") (pinfunction "1_1") (pintype "passive"))
      (node (ref "C18") (pin "2") (pinfunction "2_2") (pintype "passive"))
      (node (ref "C19") (pin "1") (pinfunction "1_1") (pintype "passive"))
      (node (ref "C2") (pin "1") (pinfunction "1_1") (pintype "passive"))
      (node (ref "C20") (pin "1") (pinfunction "1_1") (pintype "passive"))
      (node (ref "C22") (pin "2") (pinfunction "2_2") (pintype "passive"))
      (node (ref "C23") (pin "2") (pinfunction "2_2") (pintype "passive"))
      (node (ref "C24") (pin "2") (pinfunction "2_2") (pintype "passive"))
      (node (ref "C25") (pin "2") (pinfunction "2_2") (pintype "passive"))
      (node (ref "C26") (pin "1") (pinfunction "1_1") (pintype "passive"))
      (node (ref "C27") (pin "1") (pinfunction "1_1") (pintype "passive"))
      (node (ref "C28") (pin "1") (pinfunction "1_1") (pintype "passive"))
      (node (ref "C3") (pin "1") (pinfunction "1_1") (pintype "passive"))
      (node (ref "C4") (pin "1") (pinfunction "1_1") (pintype "passive"))
      (node (ref "C5") (pin "1") (pinfunction "1_1") (pintype "passive"))
      (node (ref "C6") (pin "1") (pinfunction "1_1") (pintype "passive"))
      (node (ref "C7") (pin "1") (pinfunction "1_1") (pintype "passive"))
      (node (ref "C8") (pin "1") (pinfunction "1_1") (pintype "passive"))
      (node (ref "C9") (pin "2") (pinfunction "2_2") (pintype "passive"))
      (node (ref "D10") (pin "2") (pinfunction "2_2") (pintype "passive"))
      (node (ref "J1") (pin "2") (pinfunction "GND_2") (pintype "passive"))
      (node (ref "J1") (pin "3") (pinfunction "GND_3") (pintype "passive"))
      (node (ref "J2") (pin "6") (pinfunction "6_6") (pintype "passive"))
      (node (ref "Q1") (pin "8") (pinfunction "GND_8") (pintype "passive"))
      (node (ref "Q2") (pin "2") (pinfunction "E_2") (pintype "passive"))
      (node (ref "R17") (pin "1") (pinfunction "1_1") (pintype "passive"))
      (node (ref "R22") (pin "2") (pinfunction "2_2") (pintype "passive"))
      (node (ref "R24") (pin "2") (pinfunction "2_2") (pintype "passive"))
      (node (ref "R26") (pin "2") (pinfunction "2_2") (pintype "passive"))
      (node (ref "SW1") (pin "2") (pinfunction "C_2") (pintype "passive"))
      (node (ref "SW1") (pin "5") (pinfunction "D_5") (pintype "passive"))
      (node (ref "SW1") (pin "SH1") (pinfunction "SH1_SH1") (pintype "passive"))
      (node (ref "SW1") (pin "SH2") (pinfunction "SH2_SH2") (pintype "passive"))
      (node (ref "SW2") (pin "1") (pinfunction "P1_1") (pintype "passive"))
      (node (ref "SW2") (pin "4") (pinfunction "P2_4") (pintype "passive"))
      (node (ref "SW3") (pin "1") (pinfunction "P1_1") (pintype "passive"))
      (node (ref "U1") (pin "10") (pinfunction "NC_10") (pintype "passive"))
      (node (ref "U1") (pin "11") (pinfunction "NC_11") (pintype "passive"))
      (node (ref "U1") (pin "12") (pinfunction "NC_12") (pintype "passive"))
      (node (ref "U1") (pin "13") (pinfunction "GND_13") (pintype "power_in"))
      (node (ref "U1") (pin "5") (pinfunction "NC_5") (pintype "passive"))
      (node (ref "U1") (pin "6") (pinfunction "NC_6") (pintype "passive"))
      (node (ref "U1") (pin "7") (pinfunction "NC_7") (pintype "passive"))
      (node (ref "U1") (pin "8") (pinfunction "NC_8") (pintype "passive"))
      (node (ref "U1") (pin "9") (pinfunction "NC_9") (pintype "passive"))
      (node (ref "U2") (pin "1") (pinfunction "GND_1") (pintype "power_in"))
      (node (ref "U3") (pin "1") (pinfunction "A0_1") (pintype "passive"))
      (node (ref "U3") (pin "2") (pinfunction "A1_2") (pintype "passive"))
      (node (ref "U3") (pin "3") (pinfunction "A2_3") (pintype "passive"))
      (node (ref "U3") (pin "4") (pinfunction "GND_4") (pintype "passive"))
      (node (ref "U4") (pin "1") (pinfunction "~{OE1}_1") (pintype "input"))
      (node (ref "U4") (pin "10") (pinfunction "GND_10") (pintype "passive"))
      (node (ref "U4") (pin "19") (pinfunction "~{OE2}_19") (pintype "input"))
      (node (ref "U5") (pin "1") (pinfunction "GND_1") (pintype "power_in"))
      (node (ref "U6") (pin "1") (pinfunction "GND_1") (pintype "passive"))
      (node (ref "U7") (pin "23") (pinfunction "VSS_1_23") (pintype "passive"))
      (node (ref "U7") (pin "35") (pinfunction "VSS_2_35") (pintype "passive"))
      (node (ref "U7") (pin "47") (pinfunction "VSS_3_47") (pintype "passive"))
      (node (ref "U7") (pin "8") (pinfunction "VSSA_8") (pintype "passive"))
    )
    (net (code "46") (name "Net-(BT1-POS)") (class "Default")
      (node (ref "BT1") (pin "2") (pinfunction "POS_2") (pintype "passive"))
      (node (ref "U1") (pin "14") (pinfunction "VBAT_14") (pintype "power_in"))
    )
    (net (code "47") (name "Net-(BZ1-B)") (class "Default")
      (node (ref "BZ1") (pin "2") (pinfunction "B_2") (pintype "passive"))
      (node (ref "D4") (pin "1") (pintype "passive"))
      (node (ref "Q2") (pin "3") (pinfunction "C_3") (pintype "passive"))
    )
    (net (code "48") (name "Net-(C21-Pad1)") (class "Default")
      (node (ref "C21") (pin "1") (pinfunction "1_1") (pintype "passive"))
      (node (ref "R20") (pin "2") (pinfunction "2_2") (pintype "passive"))
      (node (ref "R21") (pin "1") (pinfunction "1_1") (pintype "passive"))
    )
    (net (code "49") (name "Net-(D2-ANODE)") (class "Default")
      (node (ref "D2") (pin "1") (pinfunction "ANODE_1") (pintype "passive"))
      (node (ref "R2") (pin "2") (pinfunction "2_2") (pintype "passive"))
    )
    (net (code "50") (name "Net-(D3-ANODE)") (class "Default")
      (node (ref "D3") (pin "1") (pinfunction "ANODE_1") (pintype "passive"))
      (node (ref "R11") (pin "2") (pinfunction "2_2") (pintype "passive"))
    )
    (net (code "51") (name "Net-(D6-ANODE)") (class "Default")
      (node (ref "D6") (pin "1") (pinfunction "ANODE_1") (pintype "passive"))
      (node (ref "R16") (pin "2") (pinfunction "2_2") (pintype "passive"))
    )
    (net (code "52") (name "Net-(D7-ANODE)") (class "Default")
      (node (ref "D7") (pin "1") (pinfunction "ANODE_1") (pintype "passive"))
      (node (ref "R18") (pin "2") (pinfunction "2_2") (pintype "passive"))
    )
    (net (code "53") (name "Net-(D9-Pad1)") (class "Default")
      (node (ref "D9") (pin "1") (pinfunction "1_1") (pintype "passive"))
      (node (ref "F1") (pin "2") (pinfunction "2_2") (pintype "passive"))
    )
    (net (code "54") (name "Net-(J1-VCC)") (class "Default")
      (node (ref "F1") (pin "1") (pinfunction "1_1") (pintype "passive"))
      (node (ref "J1") (pin "1") (pinfunction "VCC_1") (pintype "passive"))
    )
    (net (code "55") (name "Net-(Q1-O1)") (class "Default")
      (node (ref "Q1") (pin "16") (pinfunction "O1_16") (pintype "passive"))
      (node (ref "R1") (pin "1") (pinfunction "1_1") (pintype "passive"))
    )
    (net (code "56") (name "Net-(Q1-O2)") (class "Default")
      (node (ref "Q1") (pin "15") (pinfunction "O2_15") (pintype "passive"))
      (node (ref "R3") (pin "1") (pinfunction "1_1") (pintype "passive"))
    )
    (net (code "57") (name "Net-(Q1-O3)") (class "Default")
      (node (ref "Q1") (pin "14") (pinfunction "O3_14") (pintype "passive"))
      (node (ref "R5") (pin "1") (pinfunction "1_1") (pintype "passive"))
    )
    (net (code "58") (name "Net-(Q1-O4)") (class "Default")
      (node (ref "Q1") (pin "13") (pinfunction "O4_13") (pintype "passive"))
      (node (ref "R6") (pin "1") (pinfunction "1_1") (pintype "passive"))
    )
    (net (code "59") (name "Net-(Q1-O5)") (class "Default")
      (node (ref "Q1") (pin "12") (pinfunction "O5_12") (pintype "passive"))
      (node (ref "R10") (pin "1") (pinfunction "1_1") (pintype "passive"))
    )
    (net (code "60") (name "Net-(Q1-O6)") (class "Default")
      (node (ref "Q1") (pin "11") (pinfunction "O6_11") (pintype "passive"))
      (node (ref "R12") (pin "1") (pinfunction "1_1") (pintype "passive"))
    )
    (net (code "61") (name "Net-(Q1-O7)") (class "Default")
      (node (ref "Q1") (pin "10") (pinfunction "O7_10") (pintype "passive"))
      (node (ref "R13") (pin "1") (pinfunction "1_1") (pintype "passive"))
    )
    (net (code "62") (name "Net-(Q2-B)") (class "Default")
      (node (ref "Q2") (pin "1") (pinfunction "B_1") (pintype "passive"))
      (node (ref "R15") (pin "2") (pinfunction "2_2") (pintype "passive"))
      (node (ref "R17") (pin "2") (pinfunction "2_2") (pintype "passive"))
    )
    (net (code "63") (name "Net-(U5-BOOT)") (class "Default")
      (node (ref "C15") (pin "2") (pinfunction "2_2") (pintype "passive"))
      (node (ref "U5") (pin "6") (pinfunction "BOOT_6") (pintype "output"))
    )
    (net (code "64") (name "Net-(U5-FB)") (class "Default")
      (node (ref "C21") (pin "2") (pinfunction "2_2") (pintype "passive"))
      (node (ref "R21") (pin "2") (pinfunction "2_2") (pintype "passive"))
      (node (ref "R22") (pin "1") (pinfunction "1_1") (pintype "passive"))
      (node (ref "U5") (pin "4") (pinfunction "FB_4") (pintype "input"))
    )
    (net (code "65") (name "Net-(U5-SW)") (class "Default")
      (node (ref "C15") (pin "1") (pinfunction "1_1") (pintype "passive"))
      (node (ref "L1") (pin "1") (pinfunction "1_1") (pintype "passive"))
      (node (ref "U5") (pin "2") (pinfunction "SW_2") (pintype "output"))
    )
    (net (code "66") (name "Net-(U7-BOOT0)") (class "Default")
      (node (ref "R24") (pin "1") (pinfunction "1_1") (pintype "passive"))
      (node (ref "U7") (pin "44") (pinfunction "BOOT0_44") (pintype "passive"))
    )
    (net (code "67") (name "Net-(U7-PB2{slash}BOOT1)") (class "Default")
      (node (ref "R26") (pin "1") (pinfunction "1_1") (pintype "passive"))
      (node (ref "U7") (pin "20") (pinfunction "PB2/BOOT1_20") (pintype "passive"))
    )
    (net (code "68") (name "Net-(U7-PD0{slash}OSC_IN)") (class "Default")
      (node (ref "C22") (pin "1") (pinfunction "1_1") (pintype "passive"))
      (node (ref "U7") (pin "5") (pinfunction "PD0/OSC_IN_5") (pintype "bidirectional"))
      (node (ref "X1") (pin "2") (pinfunction "OSC2_2") (pintype "passive"))
    )
    (net (code "69") (name "Net-(U7-PD1{slash}OSC_OUT)") (class "Default")
      (node (ref "C23") (pin "1") (pinfunction "1_1") (pintype "passive"))
      (node (ref "U7") (pin "6") (pinfunction "PD1/OSC_OUT_6") (pintype "bidirectional"))
      (node (ref "X1") (pin "1") (pinfunction "OSC1_1") (pintype "passive"))
    )
    (net (code "70") (name "unconnected-(D1-DP-Pad2)") (class "Default")
      (node (ref "D1") (pin "2") (pinfunction "DP_2") (pintype "passive+no_connect"))
    )
    (net (code "71") (name "unconnected-(D5-DP-Pad2)") (class "Default")
      (node (ref "D5") (pin "2") (pinfunction "DP_2") (pintype "passive+no_connect"))
    )
    (net (code "72") (name "unconnected-(D8-DP-Pad2)") (class "Default")
      (node (ref "D8") (pin "2") (pinfunction "DP_2") (pintype "passive+no_connect"))
    )
    (net (code "73") (name "unconnected-(Q1-COM-Pad9)") (class "Default")
      (node (ref "Q1") (pin "9") (pinfunction "COM_9") (pintype "passive+no_connect"))
    )
    (net (code "74") (name "unconnected-(U1-32KHZ-Pad1)") (class "Default")
      (node (ref "U1") (pin "1") (pinfunction "32KHZ_1") (pintype "output+no_connect"))
    )
    (net (code "75") (name "unconnected-(U1-~{RST}-Pad4)") (class "Default")
      (node (ref "U1") (pin "4") (pinfunction "~{RST}_4") (pintype "input+no_connect"))
    )
    (net (code "76") (name "unconnected-(U4-A7-Pad9)") (class "Default")
      (node (ref "U4") (pin "9") (pinfunction "A7_9") (pintype "input+no_connect"))
    )
    (net (code "77") (name "unconnected-(U4-Y7-Pad11)") (class "Default")
      (node (ref "U4") (pin "11") (pinfunction "Y7_11") (pintype "output+no_connect"))
    )
    (net (code "78") (name "unconnected-(U7-PA9{slash}USART1_TX{slash}TIM1_CH2-Pad30)") (class "Default")
      (node (ref "U7") (pin "30") (pinfunction "PA9/USART1_TX/TIM1_CH2_30") (pintype "bidirectional+no_connect"))
    )
    (net (code "79") (name "unconnected-(U7-PA11{slash}USART1_CTS{slash}CANRX{slash}USBDM{slash}TIM1_CH4-Pad32)") (class "Default")
      (node (ref "U7") (pin "32") (pinfunction "PA11/USART1_CTS/CANRX/USBDM/TIM1_CH4_32") (pintype "bidirectional+no_connect"))
    )
    (net (code "80") (name "unconnected-(U7-PB10{slash}I2C2_SCL{slash}USART3_TX-Pad21)") (class "Default")
      (node (ref "U7") (pin "21") (pinfunction "PB10/I2C2_SCL/USART3_TX_21") (pintype "bidirectional+no_connect"))
    )
    (net (code "81") (name "unconnected-(U7-PB11{slash}I2C2_SDA{slash}USART3_RX-Pad22)") (class "Default")
      (node (ref "U7") (pin "22") (pinfunction "PB11/I2C2_SDA/USART3_RX_22") (pintype "bidirectional+no_connect"))
    )
    (net (code "82") (name "unconnected-(U7-PB12{slash}SPI2_NSS{slash}I2C2_SMBAl{slash}USART3_CK{slash}TIM1_BKIN-Pad25)") (class "Default")
      (node (ref "U7") (pin "25") (pinfunction "PB12/SPI2_NSS/I2C2_SMBAl/USART3_CK/TIM1_BKIN_25") (pintype "bidirectional+no_connect"))
    )
    (net (code "83") (name "unconnected-(U7-PB15{slash}SPI2_MOSI{slash}TIM1_CH3N-Pad28)") (class "Default")
      (node (ref "U7") (pin "28") (pinfunction "PB15/SPI2_MOSI/TIM1_CH3N_28") (pintype "bidirectional+no_connect"))
    )
    (net (code "84") (name "unconnected-(U7-PC14{slash}OSC32_IN-Pad3)") (class "Default")
      (node (ref "U7") (pin "3") (pinfunction "PC14/OSC32_IN_3") (pintype "bidirectional+no_connect"))
    )
    (net (code "85") (name "unconnected-(U7-PC15{slash}OSC32_OUT-Pad4)") (class "Default")
      (node (ref "U7") (pin "4") (pinfunction "PC15/OSC32_OUT_4") (pintype "bidirectional+no_connect"))
    )
  )
)
